# Decoder_35.net
KiCad netlist of a schematic drawn in EAGLE
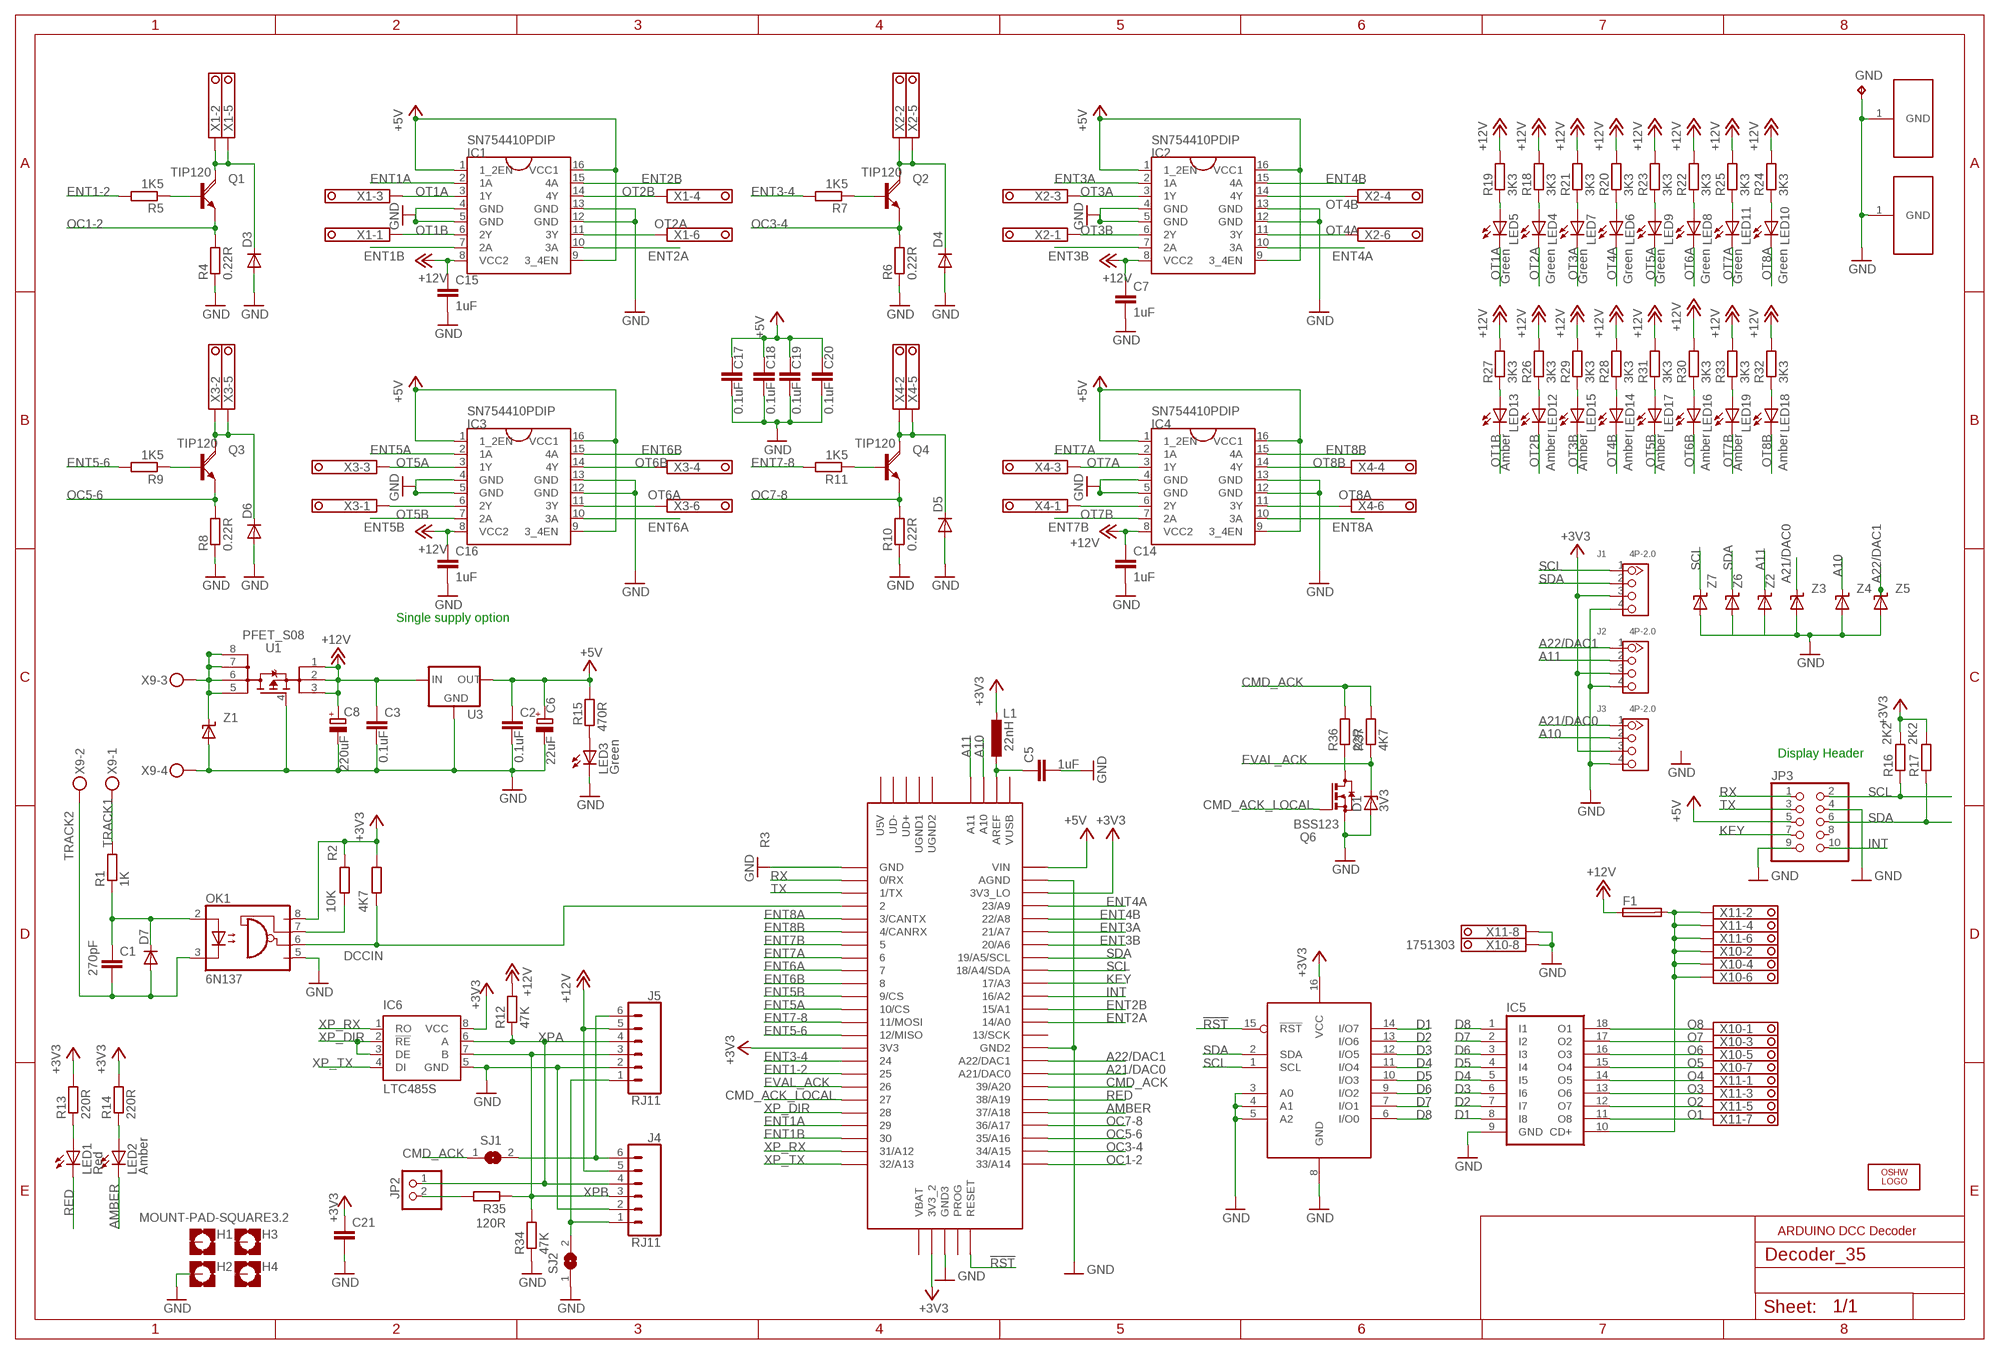
[diagram p0: schematic, sheet 1]

(export (version "E")
  (design (tool "Eeschema 10.0.6"))
  (components
    (comp (ref "C1")
      (value "270pF")
      (footprint "eagle-import:C0805")
      (libsource (lib "eagle-import") (part "rcl_334_C-EUC0805"))
    )
    (comp (ref "C2")
      (value "0.1uF")
      (footprint "eagle-import:C0805")
      (libsource (lib "eagle-import") (part "rcl_334_C-EUC0805"))
    )
    (comp (ref "C3")
      (value "0.1uF")
      (footprint "eagle-import:C0805")
      (libsource (lib "eagle-import") (part "rcl_334_C-EUC0805"))
    )
    (comp (ref "C5")
      (value "1uF")
      (footprint "eagle-import:C0805")
      (libsource (lib "eagle-import") (part "rcl_334_C-EUC0805"))
    )
    (comp (ref "C6")
      (value "22uF")
      (footprint "eagle-import:E2,5-5")
      (libsource (lib "eagle-import") (part "CPOL-EUE2.5-5"))
    )
    (comp (ref "C7")
      (value "1uF")
      (footprint "eagle-import:C0805")
      (libsource (lib "eagle-import") (part "rcl_334_C-EUC0805"))
    )
    (comp (ref "C8")
      (value "220uF")
      (footprint "eagle-import:E5-8,5")
      (libsource (lib "eagle-import") (part "CPOL-EUE5-8.5"))
    )
    (comp (ref "C14")
      (value "1uF")
      (footprint "eagle-import:C0805")
      (libsource (lib "eagle-import") (part "rcl_334_C-EUC0805"))
    )
    (comp (ref "C15")
      (value "1uF")
      (footprint "eagle-import:C0805")
      (libsource (lib "eagle-import") (part "rcl_334_C-EUC0805"))
    )
    (comp (ref "C16")
      (value "1uF")
      (footprint "eagle-import:C0805")
      (libsource (lib "eagle-import") (part "rcl_334_C-EUC0805"))
    )
    (comp (ref "C17")
      (value "0.1uF")
      (footprint "eagle-import:C0805")
      (libsource (lib "eagle-import") (part "rcl_334_C-EUC0805"))
    )
    (comp (ref "C18")
      (value "0.1uF")
      (footprint "eagle-import:C0805")
      (libsource (lib "eagle-import") (part "rcl_334_C-EUC0805"))
    )
    (comp (ref "C19")
      (value "0.1uF")
      (footprint "eagle-import:C0805")
      (libsource (lib "eagle-import") (part "rcl_334_C-EUC0805"))
    )
    (comp (ref "C20")
      (value "0.1uF")
      (footprint "eagle-import:C0805")
      (libsource (lib "eagle-import") (part "rcl_334_C-EUC0805"))
    )
    (comp (ref "C21")
      (value "C-EUC0805")
      (footprint "eagle-import:C0805")
      (libsource (lib "eagle-import") (part "C-EUC0805"))
    )
    (comp (ref "D1")
      (value "3V3")
      (footprint "eagle-import:SOT23")
      (libsource (lib "eagle-import") (part "ZENER-DIODESOT23"))
    )
    (comp (ref "D3")
      (value "CGRM4002-G")
      (footprint "eagle-import:SOD-123_MINI-SMA")
      (libsource (lib "eagle-import") (part "CGRM400-G2"))
    )
    (comp (ref "D4")
      (value "CGRM4002-G")
      (footprint "eagle-import:SOD-123_MINI-SMA")
      (libsource (lib "eagle-import") (part "CGRM400-G2"))
    )
    (comp (ref "D5")
      (value "CGRM4002-G")
      (footprint "eagle-import:SOD-123_MINI-SMA")
      (libsource (lib "eagle-import") (part "CGRM400-G2"))
    )
    (comp (ref "D6")
      (value "CGRM4002-G")
      (footprint "eagle-import:SOD-123_MINI-SMA")
      (libsource (lib "eagle-import") (part "CGRM400-G2"))
    )
    (comp (ref "D7")
      (value "CGRM4002-G")
      (footprint "eagle-import:SOD-123_MINI-SMA")
      (libsource (lib "eagle-import") (part "CGRM400-G2"))
    )
    (comp (ref "F1")
      (value "SMD_FUSE")
      (footprint "eagle-import:1812")
      (fields (field (name "MANUFACTURER") "Littelfuse"))
      (libsource (lib "eagle-import") (part "SMD_FUSE"))
    )
    (comp (ref "GND")
      (value "TPB2,54")
      (footprint "eagle-import:B2,54")
      (libsource (lib "eagle-import") (part "TPB2,54"))
    )
    (comp (ref "H1")
      (value "MOUNT-PAD-SQUARE3.2")
      (footprint "eagle-import:3,2-PAD-SQUARE")
      (libsource (lib "eagle-import") (part "MOUNT-PAD-SQUARE3.2"))
    )
    (comp (ref "H2")
      (value "MOUNT-PAD-SQUARE3.2")
      (footprint "eagle-import:3,2-PAD-SQUARE")
      (libsource (lib "eagle-import") (part "MOUNT-PAD-SQUARE3.2"))
    )
    (comp (ref "H3")
      (value "MOUNT-PAD-SQUARE3.2")
      (footprint "eagle-import:3,2-PAD-SQUARE")
      (libsource (lib "eagle-import") (part "MOUNT-PAD-SQUARE3.2"))
    )
    (comp (ref "H4")
      (value "MOUNT-PAD-SQUARE3.2")
      (footprint "eagle-import:3,2-PAD-SQUARE")
      (libsource (lib "eagle-import") (part "MOUNT-PAD-SQUARE3.2"))
    )
    (comp (ref "IC1")
      (value "SN754410PDIP")
      (footprint "eagle-import:DIL16")
      (libsource (lib "eagle-import") (part "SN754410PDIP"))
    )
    (comp (ref "IC2")
      (value "SN754410PDIP")
      (footprint "eagle-import:DIL16")
      (libsource (lib "eagle-import") (part "SN754410PDIP"))
    )
    (comp (ref "IC3")
      (value "SN754410PDIP")
      (footprint "eagle-import:DIL16")
      (libsource (lib "eagle-import") (part "SN754410PDIP"))
    )
    (comp (ref "IC4")
      (value "SN754410PDIP")
      (footprint "eagle-import:DIL16")
      (libsource (lib "eagle-import") (part "SN754410PDIP"))
    )
    (comp (ref "IC5")
      (value "ULN2803A")
      (footprint "eagle-import:DIL18")
      (libsource (lib "eagle-import") (part "ULN2803A"))
    )
    (comp (ref "IC6")
      (value "LTC485S")
      (footprint "eagle-import:SOIC8")
      (libsource (lib "eagle-import") (part "LTC485S"))
    )
    (comp (ref "J1")
      (value "4P-2.0")
      (footprint "eagle-import:HW4-2.0")
      (libsource (lib "eagle-import") (part "GROVE-CONNECTOR-DIP(4P-2.0)"))
    )
    (comp (ref "J2")
      (value "4P-2.0")
      (footprint "eagle-import:HW4-2.0")
      (libsource (lib "eagle-import") (part "GROVE-CONNECTOR-DIP(4P-2.0)"))
    )
    (comp (ref "J3")
      (value "4P-2.0")
      (footprint "eagle-import:HW4-2.0")
      (libsource (lib "eagle-import") (part "GROVE-CONNECTOR-DIP(4P-2.0)"))
    )
    (comp (ref "J4")
      (value "RJ11")
      (footprint "eagle-import:RJ11-6")
      (libsource (lib "eagle-import") (part "RJ11-6"))
    )
    (comp (ref "J5")
      (value "RJ11")
      (footprint "eagle-import:RJ11-6")
      (libsource (lib "eagle-import") (part "RJ11-6"))
    )
    (comp (ref "JP2")
      (value "PINHD-1X2")
      (footprint "eagle-import:1X02")
      (libsource (lib "eagle-import") (part "PINHD-1X2"))
    )
    (comp (ref "JP3")
      (value "PINHD-2X5")
      (footprint "eagle-import:2X05")
      (libsource (lib "eagle-import") (part "PINHD-2X5"))
    )
    (comp (ref "L1")
      (value "22nH")
      (footprint "eagle-import:L2012C")
      (libsource (lib "eagle-import") (part "L-EUL2012C"))
    )
    (comp (ref "LED1")
      (value "Red")
      (footprint "eagle-import:LED3MM")
      (libsource (lib "eagle-import") (part "LED3MM"))
    )
    (comp (ref "LED2")
      (value "Amber")
      (footprint "eagle-import:LED3MM")
      (libsource (lib "eagle-import") (part "LED3MM"))
    )
    (comp (ref "LED3")
      (value "Green")
      (footprint "eagle-import:LED3MM")
      (libsource (lib "eagle-import") (part "LED3MM"))
    )
    (comp (ref "LED4")
      (value "Green")
      (footprint "eagle-import:LED3MM")
      (libsource (lib "eagle-import") (part "LED3MM"))
    )
    (comp (ref "LED5")
      (value "Green")
      (footprint "eagle-import:LED3MM")
      (libsource (lib "eagle-import") (part "LED3MM"))
    )
    (comp (ref "LED6")
      (value "Green")
      (footprint "eagle-import:LED3MM")
      (libsource (lib "eagle-import") (part "LED3MM"))
    )
    (comp (ref "LED7")
      (value "Green")
      (footprint "eagle-import:LED3MM")
      (libsource (lib "eagle-import") (part "LED3MM"))
    )
    (comp (ref "LED8")
      (value "Green")
      (footprint "eagle-import:LED3MM")
      (libsource (lib "eagle-import") (part "LED3MM"))
    )
    (comp (ref "LED9")
      (value "Green")
      (footprint "eagle-import:LED3MM")
      (libsource (lib "eagle-import") (part "LED3MM"))
    )
    (comp (ref "LED10")
      (value "Green")
      (footprint "eagle-import:LED3MM")
      (libsource (lib "eagle-import") (part "LED3MM"))
    )
    (comp (ref "LED11")
      (value "Green")
      (footprint "eagle-import:LED3MM")
      (libsource (lib "eagle-import") (part "LED3MM"))
    )
    (comp (ref "LED12")
      (value "Amber")
      (footprint "eagle-import:LED3MM")
      (libsource (lib "eagle-import") (part "LED3MM"))
    )
    (comp (ref "LED13")
      (value "Amber")
      (footprint "eagle-import:LED3MM")
      (libsource (lib "eagle-import") (part "LED3MM"))
    )
    (comp (ref "LED14")
      (value "Amber")
      (footprint "eagle-import:LED3MM")
      (libsource (lib "eagle-import") (part "LED3MM"))
    )
    (comp (ref "LED15")
      (value "Amber")
      (footprint "eagle-import:LED3MM")
      (libsource (lib "eagle-import") (part "LED3MM"))
    )
    (comp (ref "LED16")
      (value "Amber")
      (footprint "eagle-import:LED3MM")
      (libsource (lib "eagle-import") (part "LED3MM"))
    )
    (comp (ref "LED17")
      (value "Amber")
      (footprint "eagle-import:LED3MM")
      (libsource (lib "eagle-import") (part "LED3MM"))
    )
    (comp (ref "LED18")
      (value "Amber")
      (footprint "eagle-import:LED3MM")
      (libsource (lib "eagle-import") (part "LED3MM"))
    )
    (comp (ref "LED19")
      (value "Amber")
      (footprint "eagle-import:LED3MM")
      (libsource (lib "eagle-import") (part "LED3MM"))
    )
    (comp (ref "LOGO1")
      (value "OSHW_LOGO_6MILX0200-NT")
      (footprint "eagle-import:OSHW_6X200_NOTEXT")
      (libsource (lib "eagle-import") (part "OSHW_LOGO_6MILX0200-NT"))
    )
    (comp (ref "MT1")
      (value "DINC45_MOUNT")
      (footprint "eagle-import:DIN_C45")
      (libsource (lib "eagle-import") (part "DINC45_MOUNT"))
    )
    (comp (ref "MT2")
      (value "DINC45_MOUNT")
      (footprint "eagle-import:DIN_C45")
      (libsource (lib "eagle-import") (part "DINC45_MOUNT"))
    )
    (comp (ref "OK1")
      (value "6N137")
      (footprint "eagle-import:DIL08")
      (libsource (lib "eagle-import") (part "6N137"))
    )
    (comp (ref "Q1")
      (value "TIP120")
      (footprint "eagle-import:TO220AH")
      (libsource (lib "eagle-import") (part "TIP120"))
    )
    (comp (ref "Q2")
      (value "TIP120")
      (footprint "eagle-import:TO220AH")
      (libsource (lib "eagle-import") (part "TIP120"))
    )
    (comp (ref "Q3")
      (value "TIP120")
      (footprint "eagle-import:TO220AH")
      (libsource (lib "eagle-import") (part "TIP120"))
    )
    (comp (ref "Q4")
      (value "TIP120")
      (footprint "eagle-import:TO220AH")
      (libsource (lib "eagle-import") (part "TIP120"))
    )
    (comp (ref "Q6")
      (value "BSS123")
      (footprint "eagle-import:SOT23")
      (libsource (lib "eagle-import") (part "BSS123"))
    )
    (comp (ref "R1")
      (value "1K")
      (footprint "eagle-import:R0805")
      (libsource (lib "eagle-import") (part "rcl_334_R-EU_R0805"))
    )
    (comp (ref "R2")
      (value "10K")
      (footprint "eagle-import:R0805")
      (libsource (lib "eagle-import") (part "rcl_334_R-EU_R0805"))
    )
    (comp (ref "R3")
      (value "4K7")
      (footprint "eagle-import:R0805")
      (libsource (lib "eagle-import") (part "rcl_334_R-EU_R0805"))
    )
    (comp (ref "R4")
      (value "0.22R")
      (footprint "eagle-import:R2512")
      (libsource (lib "eagle-import") (part "rcl_334_R-EU_R2512"))
    )
    (comp (ref "R5")
      (value "1K5")
      (footprint "eagle-import:R0805")
      (libsource (lib "eagle-import") (part "rcl_334_R-EU_R0805"))
    )
    (comp (ref "R6")
      (value "0.22R")
      (footprint "eagle-import:R2512")
      (libsource (lib "eagle-import") (part "rcl_334_R-EU_R2512"))
    )
    (comp (ref "R7")
      (value "1K5")
      (footprint "eagle-import:R0805")
      (libsource (lib "eagle-import") (part "rcl_334_R-EU_R0805"))
    )
    (comp (ref "R8")
      (value "0.22R")
      (footprint "eagle-import:R2512")
      (libsource (lib "eagle-import") (part "rcl_334_R-EU_R2512"))
    )
    (comp (ref "R9")
      (value "1K5")
      (footprint "eagle-import:R0805")
      (libsource (lib "eagle-import") (part "rcl_334_R-EU_R0805"))
    )
    (comp (ref "R10")
      (value "0.22R")
      (footprint "eagle-import:R2512")
      (libsource (lib "eagle-import") (part "rcl_334_R-EU_R2512"))
    )
    (comp (ref "R11")
      (value "1K5")
      (footprint "eagle-import:R0805")
      (libsource (lib "eagle-import") (part "rcl_334_R-EU_R0805"))
    )
    (comp (ref "R12")
      (value "47K")
      (footprint "eagle-import:R0805")
      (libsource (lib "eagle-import") (part "R-EU_R0805"))
    )
    (comp (ref "R13")
      (value "220R")
      (footprint "eagle-import:R0805")
      (libsource (lib "eagle-import") (part "rcl_334_R-EU_R0805"))
    )
    (comp (ref "R14")
      (value "220R")
      (footprint "eagle-import:R0805")
      (libsource (lib "eagle-import") (part "rcl_334_R-EU_R0805"))
    )
    (comp (ref "R15")
      (value "470R")
      (footprint "eagle-import:R0805")
      (libsource (lib "eagle-import") (part "rcl_334_R-EU_R0805"))
    )
    (comp (ref "R16")
      (value "2K2")
      (footprint "eagle-import:R0805")
      (libsource (lib "eagle-import") (part "rcl_334_R-EU_R0805"))
    )
    (comp (ref "R17")
      (value "2K2")
      (footprint "eagle-import:R0805")
      (libsource (lib "eagle-import") (part "rcl_334_R-EU_R0805"))
    )
    (comp (ref "R18")
      (value "3K3")
      (footprint "eagle-import:R0805")
      (libsource (lib "eagle-import") (part "rcl_334_R-EU_R0805"))
    )
    (comp (ref "R19")
      (value "3K3")
      (footprint "eagle-import:R0805")
      (libsource (lib "eagle-import") (part "rcl_334_R-EU_R0805"))
    )
    (comp (ref "R20")
      (value "3K3")
      (footprint "eagle-import:R0805")
      (libsource (lib "eagle-import") (part "rcl_334_R-EU_R0805"))
    )
    (comp (ref "R21")
      (value "3K3")
      (footprint "eagle-import:R0805")
      (libsource (lib "eagle-import") (part "rcl_334_R-EU_R0805"))
    )
    (comp (ref "R22")
      (value "3K3")
      (footprint "eagle-import:R0805")
      (libsource (lib "eagle-import") (part "rcl_334_R-EU_R0805"))
    )
    (comp (ref "R23")
      (value "3K3")
      (footprint "eagle-import:R0805")
      (libsource (lib "eagle-import") (part "rcl_334_R-EU_R0805"))
    )
    (comp (ref "R24")
      (value "3K3")
      (footprint "eagle-import:R0805")
      (libsource (lib "eagle-import") (part "rcl_334_R-EU_R0805"))
    )
    (comp (ref "R25")
      (value "3K3")
      (footprint "eagle-import:R0805")
      (libsource (lib "eagle-import") (part "rcl_334_R-EU_R0805"))
    )
    (comp (ref "R26")
      (value "3K3")
      (footprint "eagle-import:R0805")
      (libsource (lib "eagle-import") (part "rcl_334_R-EU_R0805"))
    )
    (comp (ref "R27")
      (value "3K3")
      (footprint "eagle-import:R0805")
      (libsource (lib "eagle-import") (part "rcl_334_R-EU_R0805"))
    )
    (comp (ref "R28")
      (value "3K3")
      (footprint "eagle-import:R0805")
      (libsource (lib "eagle-import") (part "rcl_334_R-EU_R0805"))
    )
    (comp (ref "R29")
      (value "3K3")
      (footprint "eagle-import:R0805")
      (libsource (lib "eagle-import") (part "rcl_334_R-EU_R0805"))
    )
    (comp (ref "R30")
      (value "3K3")
      (footprint "eagle-import:R0805")
      (libsource (lib "eagle-import") (part "rcl_334_R-EU_R0805"))
    )
    (comp (ref "R31")
      (value "3K3")
      (footprint "eagle-import:R0805")
      (libsource (lib "eagle-import") (part "rcl_334_R-EU_R0805"))
    )
    (comp (ref "R32")
      (value "3K3")
      (footprint "eagle-import:R0805")
      (libsource (lib "eagle-import") (part "rcl_334_R-EU_R0805"))
    )
    (comp (ref "R33")
      (value "3K3")
      (footprint "eagle-import:R0805")
      (libsource (lib "eagle-import") (part "rcl_334_R-EU_R0805"))
    )
    (comp (ref "R34")
      (value "47K")
      (footprint "eagle-import:R0805")
      (libsource (lib "eagle-import") (part "R-EU_R0805"))
    )
    (comp (ref "R35")
      (value "120R")
      (footprint "eagle-import:R0805")
      (libsource (lib "eagle-import") (part "R-EU_R0805"))
    )
    (comp (ref "R36")
      (value "22R")
      (footprint "eagle-import:R0805")
      (libsource (lib "eagle-import") (part "R-EU_R0805"))
    )
    (comp (ref "R37")
      (value "4K7")
      (footprint "eagle-import:R0805")
      (libsource (lib "eagle-import") (part "R-EU_R0805"))
    )
    (comp (ref "SJ1") (value "SJ") (footprint "eagle-import:SJ") (libsource (lib "eagle-import") (part "SJ")))
    (comp (ref "SJ2") (value "SJ") (footprint "eagle-import:SJ") (libsource (lib "eagle-import") (part "SJ")))
    (comp (ref "U$1")
      (value "TEENSY_3.5/3.6")
      (footprint "eagle-import:TEENSY_3.5_3.6")
      (libsource (lib "eagle-import") (part "TEENSY_3.5/3.6"))
    )
    (comp (ref "U1")
      (value "PFET_S08")
      (footprint "eagle-import:SO08")
      (fields (field (name "MANUFACTURER") "Infineon") (field (name "PARTNUMBER") "IRF9388TRFPBF"))
      (libsource (lib "eagle-import") (part "PFET_S08"))
    )
    (comp (ref "U2")
      (value "PCA9557")
      (footprint "eagle-import:S016")
      (libsource (lib "eagle-import") (part "PCA9557"))
    )
    (comp (ref "U3")
      (value "V_REG_78XX-TO-220")
      (footprint "eagle-import:TO-220-ALT")
      (libsource (lib "eagle-import") (part "V_REG_78XX-TO-220"))
    )
    (comp (ref "X1")
      (value "1751280")
      (footprint "eagle-import:1751280")
      (libsource (lib "eagle-import") (part "1751280"))
    )
    (comp (ref "X2")
      (value "1751280")
      (footprint "eagle-import:1751280")
      (libsource (lib "eagle-import") (part "1751280"))
    )
    (comp (ref "X3")
      (value "1751280")
      (footprint "eagle-import:1751280")
      (libsource (lib "eagle-import") (part "1751280"))
    )
    (comp (ref "X4")
      (value "1751280")
      (footprint "eagle-import:1751280")
      (libsource (lib "eagle-import") (part "1751280"))
    )
    (comp (ref "X9")
      (value "MKDSN1,5/4-5,08")
      (footprint "eagle-import:MKDSN1,5_4-5,08")
      (libsource (lib "eagle-import") (part "MKDSN1,5/4-5,08"))
    )
    (comp (ref "X10")
      (value "1751303")
      (footprint "eagle-import:1751303")
      (libsource (lib "eagle-import") (part "1751303"))
    )
    (comp (ref "X11")
      (value "1751303")
      (footprint "eagle-import:1751303")
      (libsource (lib "eagle-import") (part "1751303"))
    )
    (comp (ref "Z1")
      (value "TRANSZORB")
      (footprint "eagle-import:SMB")
      (fields (field (name "VOLTAGE") "15V"))
      (libsource (lib "eagle-import") (part "TRANSZORB"))
    )
    (comp (ref "Z2")
      (value "TRANSZORB-SMA")
      (footprint "eagle-import:SMA")
      (libsource (lib "eagle-import") (part "TRANSZORB-SMA"))
    )
    (comp (ref "Z3")
      (value "TRANSZORB-SMA")
      (footprint "eagle-import:SMA")
      (libsource (lib "eagle-import") (part "TRANSZORB-SMA"))
    )
    (comp (ref "Z4")
      (value "TRANSZORB-SMA")
      (footprint "eagle-import:SMA")
      (libsource (lib "eagle-import") (part "TRANSZORB-SMA"))
    )
    (comp (ref "Z5")
      (value "TRANSZORB-SMA")
      (footprint "eagle-import:SMA")
      (libsource (lib "eagle-import") (part "TRANSZORB-SMA"))
    )
    (comp (ref "Z6")
      (value "TRANSZORB-SMA")
      (footprint "eagle-import:SMA")
      (libsource (lib "eagle-import") (part "TRANSZORB-SMA"))
    )
    (comp (ref "Z7")
      (value "TRANSZORB-SMA")
      (footprint "eagle-import:SMA")
      (libsource (lib "eagle-import") (part "TRANSZORB-SMA"))
    )
  )
  (nets
    (net (code "1") (name "+3V3") (class "Default")
      (node (ref "C21") (pin "1") (pinfunction "1_1") (pintype "passive"))
      (node (ref "IC6") (pin "8") (pinfunction "VCC_8") (pintype "input"))
      (node (ref "J1") (pin "3") (pinfunction "3_3") (pintype "bidirectional"))
      (node (ref "J2") (pin "3") (pinfunction "3_3") (pintype "bidirectional"))
      (node (ref "J3") (pin "3") (pinfunction "3_3") (pintype "bidirectional"))
      (node (ref "L1") (pin "1") (pinfunction "1_1") (pintype "passive"))
      (node (ref "OK1") (pin "8") (pinfunction "VCC_8") (pintype "passive"))
      (node (ref "R13") (pin "2") (pinfunction "2_2") (pintype "passive"))
      (node (ref "R14") (pin "2") (pinfunction "2_2") (pintype "passive"))
      (node (ref "R16") (pin "2") (pinfunction "2_2") (pintype "passive"))
      (node (ref "R17") (pin "2") (pinfunction "2_2") (pintype "passive"))
      (node (ref "R2") (pin "2") (pinfunction "2_2") (pintype "passive"))
      (node (ref "R3") (pin "2") (pinfunction "2_2") (pintype "passive"))
      (node (ref "U$1") (pin "3V3") (pinfunction "3V3_3V3") (pintype "bidirectional"))
      (node (ref "U$1") (pin "3V3_2") (pinfunction "3V3_2_3V3_2") (pintype "bidirectional"))
      (node (ref "U$1") (pin "3V3_LO") (pinfunction "3V3_LO_3V3_LO") (pintype "bidirectional"))
      (node (ref "U2") (pin "16") (pinfunction "VCC_16") (pintype "power_in"))
    )
    (net (code "2") (name "+5V") (class "Default")
      (node (ref "C17") (pin "1") (pinfunction "1_1") (pintype "passive"))
      (node (ref "C18") (pin "1") (pinfunction "1_1") (pintype "passive"))
      (node (ref "C19") (pin "1") (pinfunction "1_1") (pintype "passive"))
      (node (ref "C2") (pin "1") (pinfunction "1_1") (pintype "passive"))
      (node (ref "C20") (pin "1") (pinfunction "1_1") (pintype "passive"))
      (node (ref "C6") (pin "+") (pinfunction "+_+") (pintype "passive"))
      (node (ref "IC1") (pin "1") (pinfunction "1_2EN_1") (pintype "bidirectional"))
      (node (ref "IC1") (pin "16") (pinfunction "VCC1_16") (pintype "bidirectional"))
      (node (ref "IC1") (pin "9") (pinfunction "3_4EN_9") (pintype "bidirectional"))
      (node (ref "IC2") (pin "1") (pinfunction "1_2EN_1") (pintype "bidirectional"))
      (node (ref "IC2") (pin "16") (pinfunction "VCC1_16") (pintype "bidirectional"))
      (node (ref "IC2") (pin "9") (pinfunction "3_4EN_9") (pintype "bidirectional"))
      (node (ref "IC3") (pin "1") (pinfunction "1_2EN_1") (pintype "bidirectional"))
      (node (ref "IC3") (pin "16") (pinfunction "VCC1_16") (pintype "bidirectional"))
      (node (ref "IC3") (pin "9") (pinfunction "3_4EN_9") (pintype "bidirectional"))
      (node (ref "IC4") (pin "1") (pinfunction "1_2EN_1") (pintype "bidirectional"))
      (node (ref "IC4") (pin "16") (pinfunction "VCC1_16") (pintype "bidirectional"))
      (node (ref "IC4") (pin "9") (pinfunction "3_4EN_9") (pintype "bidirectional"))
      (node (ref "JP3") (pin "5") (pinfunction "5_5") (pintype "passive"))
      (node (ref "R15") (pin "2") (pinfunction "2_2") (pintype "passive"))
      (node (ref "U$1") (pin "VIN") (pinfunction "VIN_VIN") (pintype "bidirectional"))
      (node (ref "U3") (pin "OUT") (pinfunction "OUT_OUT") (pintype "passive"))
    )
    (net (code "3") (name "+12V") (class "Default")
      (node (ref "C14") (pin "1") (pinfunction "1_1") (pintype "passive"))
      (node (ref "C15") (pin "1") (pinfunction "1_1") (pintype "passive"))
      (node (ref "C16") (pin "1") (pinfunction "1_1") (pintype "passive"))
      (node (ref "C3") (pin "1") (pinfunction "1_1") (pintype "passive"))
      (node (ref "C7") (pin "1") (pinfunction "1_1") (pintype "passive"))
      (node (ref "C8") (pin "+") (pinfunction "+_+") (pintype "passive"))
      (node (ref "F1") (pin "1") (pinfunction "1_1") (pintype "passive"))
      (node (ref "IC1") (pin "8") (pinfunction "VCC2_8") (pintype "bidirectional"))
      (node (ref "IC2") (pin "8") (pinfunction "VCC2_8") (pintype "bidirectional"))
      (node (ref "IC3") (pin "8") (pinfunction "VCC2_8") (pintype "bidirectional"))
      (node (ref "IC4") (pin "8") (pinfunction "VCC2_8") (pintype "bidirectional"))
      (node (ref "J4") (pin "5") (pinfunction "5_5") (pintype "passive"))
      (node (ref "J5") (pin "5") (pinfunction "5_5") (pintype "passive"))
      (node (ref "R12") (pin "2") (pinfunction "2_2") (pintype "passive"))
      (node (ref "R18") (pin "2") (pinfunction "2_2") (pintype "passive"))
      (node (ref "R19") (pin "2") (pinfunction "2_2") (pintype "passive"))
      (node (ref "R20") (pin "2") (pinfunction "2_2") (pintype "passive"))
      (node (ref "R21") (pin "2") (pinfunction "2_2") (pintype "passive"))
      (node (ref "R22") (pin "2") (pinfunction "2_2") (pintype "passive"))
      (node (ref "R23") (pin "2") (pinfunction "2_2") (pintype "passive"))
      (node (ref "R24") (pin "2") (pinfunction "2_2") (pintype "passive"))
      (node (ref "R25") (pin "2") (pinfunction "2_2") (pintype "passive"))
      (node (ref "R26") (pin "2") (pinfunction "2_2") (pintype "passive"))
      (node (ref "R27") (pin "2") (pinfunction "2_2") (pintype "passive"))
      (node (ref "R28") (pin "2") (pinfunction "2_2") (pintype "passive"))
      (node (ref "R29") (pin "2") (pinfunction "2_2") (pintype "passive"))
      (node (ref "R30") (pin "2") (pinfunction "2_2") (pintype "passive"))
      (node (ref "R31") (pin "2") (pinfunction "2_2") (pintype "passive"))
      (node (ref "R32") (pin "2") (pinfunction "2_2") (pintype "passive"))
      (node (ref "R33") (pin "2") (pinfunction "2_2") (pintype "passive"))
      (node (ref "U1") (pin "1") (pinfunction "S1_1") (pintype "passive"))
      (node (ref "U1") (pin "2") (pinfunction "S2_2") (pintype "passive"))
      (node (ref "U1") (pin "3") (pinfunction "S3_3") (pintype "passive"))
      (node (ref "U3") (pin "IN") (pinfunction "IN_IN") (pintype "input"))
    )
    (net (code "4") (name "/A10") (class "Default")
      (node (ref "J3") (pin "2") (pinfunction "2_2") (pintype "bidirectional"))
      (node (ref "U$1") (pin "A10") (pinfunction "A10_A10") (pintype "bidirectional"))
      (node (ref "Z4") (pin "C") (pinfunction "C_C") (pintype "passive"))
    )
    (net (code "5") (name "/A11") (class "Default")
      (node (ref "J2") (pin "2") (pinfunction "2_2") (pintype "bidirectional"))
      (node (ref "U$1") (pin "A11") (pinfunction "A11_A11") (pintype "bidirectional"))
      (node (ref "Z2") (pin "C") (pinfunction "C_C") (pintype "passive"))
    )
    (net (code "6") (name "/A21{slash}DAC0") (class "Default")
      (node (ref "J3") (pin "1") (pinfunction "1_1") (pintype "bidirectional"))
      (node (ref "U$1") (pin "21/DAC0") (pinfunction "A21/DAC0_21/DAC0") (pintype "bidirectional"))
      (node (ref "Z3") (pin "C") (pinfunction "C_C") (pintype "passive"))
    )
    (net (code "7") (name "/A22{slash}DAC1") (class "Default")
      (node (ref "J2") (pin "1") (pinfunction "1_1") (pintype "bidirectional"))
      (node (ref "U$1") (pin "A22/DAC1") (pinfunction "A22/DAC1_A22/DAC1") (pintype "bidirectional"))
      (node (ref "Z5") (pin "C") (pinfunction "C_C") (pintype "passive"))
    )
    (net (code "8") (name "/AMBER") (class "Default")
      (node (ref "LED2") (pin "K") (pinfunction "C_K") (pintype "passive"))
      (node (ref "U$1") (pin "37/A18") (pinfunction "37/A18_37/A18") (pintype "bidirectional"))
    )
    (net (code "9") (name "/CMD_ACK") (class "Default")
      (node (ref "R36") (pin "2") (pinfunction "2_2") (pintype "passive"))
      (node (ref "R37") (pin "2") (pinfunction "2_2") (pintype "passive"))
      (node (ref "SJ1") (pin "1") (pinfunction "1_1") (pintype "passive"))
      (node (ref "U$1") (pin "39/A20") (pinfunction "39/A20_39/A20") (pintype "bidirectional"))
    )
    (net (code "10") (name "/CMD_ACK_LOCAL") (class "Default")
      (node (ref "Q6") (pin "1") (pinfunction "G_1") (pintype "passive"))
      (node (ref "U$1") (pin "27") (pinfunction "27_27") (pintype "bidirectional"))
    )
    (net (code "11") (name "/D1") (class "Default")
      (node (ref "IC5") (pin "8") (pinfunction "I8_8") (pintype "input"))
      (node (ref "U2") (pin "14") (pinfunction "I/O7_14") (pintype "bidirectional"))
    )
    (net (code "12") (name "/D2") (class "Default")
      (node (ref "IC5") (pin "7") (pinfunction "I7_7") (pintype "input"))
      (node (ref "U2") (pin "13") (pinfunction "I/O6_13") (pintype "bidirectional"))
    )
    (net (code "13") (name "/D3") (class "Default")
      (node (ref "IC5") (pin "6") (pinfunction "I6_6") (pintype "input"))
      (node (ref "U2") (pin "12") (pinfunction "I/O5_12") (pintype "bidirectional"))
    )
    (net (code "14") (name "/D4") (class "Default")
      (node (ref "IC5") (pin "5") (pinfunction "I5_5") (pintype "input"))
      (node (ref "U2") (pin "11") (pinfunction "I/O4_11") (pintype "bidirectional"))
    )
    (net (code "15") (name "/D5") (class "Default")
      (node (ref "IC5") (pin "4") (pinfunction "I4_4") (pintype "input"))
      (node (ref "U2") (pin "10") (pinfunction "I/O3_10") (pintype "bidirectional"))
    )
    (net (code "16") (name "/D6") (class "Default")
      (node (ref "IC5") (pin "3") (pinfunction "I3_3") (pintype "input"))
      (node (ref "U2") (pin "9") (pinfunction "I/O2_9") (pintype "bidirectional"))
    )
    (net (code "17") (name "/D7") (class "Default")
      (node (ref "IC5") (pin "2") (pinfunction "I2_2") (pintype "input"))
      (node (ref "U2") (pin "7") (pinfunction "I/O1_7") (pintype "bidirectional"))
    )
    (net (code "18") (name "/D8") (class "Default")
      (node (ref "IC5") (pin "1") (pinfunction "I1_1") (pintype "input"))
      (node (ref "U2") (pin "6") (pinfunction "I/O0_6") (pintype "bidirectional"))
    )
    (net (code "19") (name "/DCCIN") (class "Default")
      (node (ref "OK1") (pin "6") (pinfunction "VO_6") (pintype "passive"))
      (node (ref "R3") (pin "1") (pinfunction "1_1") (pintype "passive"))
      (node (ref "U$1") (pin "2") (pinfunction "2_2") (pintype "bidirectional"))
    )
    (net (code "20") (name "/ENT1-2") (class "Default")
      (node (ref "R5") (pin "2") (pinfunction "2_2") (pintype "passive"))
      (node (ref "U$1") (pin "25") (pinfunction "25_25") (pintype "bidirectional"))
    )
    (net (code "21") (name "/ENT1A") (class "Default")
      (node (ref "IC1") (pin "2") (pinfunction "1A_2") (pintype "bidirectional"))
      (node (ref "U$1") (pin "29") (pinfunction "29_29") (pintype "bidirectional"))
    )
    (net (code "22") (name "/ENT1B") (class "Default")
      (node (ref "IC1") (pin "7") (pinfunction "2A_7") (pintype "bidirectional"))
      (node (ref "U$1") (pin "30") (pinfunction "30_30") (pintype "bidirectional"))
    )
    (net (code "23") (name "/ENT2A") (class "Default")
      (node (ref "IC1") (pin "10") (pinfunction "3A_10") (pintype "bidirectional"))
      (node (ref "U$1") (pin "14/A0") (pinfunction "14/A0_14/A0") (pintype "bidirectional"))
    )
    (net (code "24") (name "/ENT2B") (class "Default")
      (node (ref "IC1") (pin "15") (pinfunction "4A_15") (pintype "bidirectional"))
      (node (ref "U$1") (pin "15/A1") (pinfunction "15/A1_15/A1") (pintype "bidirectional"))
    )
    (net (code "25") (name "/ENT3-4") (class "Default")
      (node (ref "R7") (pin "2") (pinfunction "2_2") (pintype "passive"))
      (node (ref "U$1") (pin "24") (pinfunction "24_24") (pintype "bidirectional"))
    )
    (net (code "26") (name "/ENT3A") (class "Default")
      (node (ref "IC2") (pin "2") (pinfunction "1A_2") (pintype "bidirectional"))
      (node (ref "U$1") (pin "21/A7") (pinfunction "21/A7_21/A7") (pintype "bidirectional"))
    )
    (net (code "27") (name "/ENT3B") (class "Default")
      (node (ref "IC2") (pin "7") (pinfunction "2A_7") (pintype "bidirectional"))
      (node (ref "U$1") (pin "20/A6") (pinfunction "20/A6_20/A6") (pintype "bidirectional"))
    )
    (net (code "28") (name "/ENT4A") (class "Default")
      (node (ref "IC2") (pin "10") (pinfunction "3A_10") (pintype "bidirectional"))
      (node (ref "U$1") (pin "23/A9") (pinfunction "23/A9_23/A9") (pintype "bidirectional"))
    )
    (net (code "29") (name "/ENT4B") (class "Default")
      (node (ref "IC2") (pin "15") (pinfunction "4A_15") (pintype "bidirectional"))
      (node (ref "U$1") (pin "22/A8") (pinfunction "22/A8_22/A8") (pintype "bidirectional"))
    )
    (net (code "30") (name "/ENT5-6") (class "Default")
      (node (ref "R9") (pin "2") (pinfunction "2_2") (pintype "passive"))
      (node (ref "U$1") (pin "12/MISO") (pinfunction "12/MISO_12/MISO") (pintype "bidirectional"))
    )
    (net (code "31") (name "/ENT5A") (class "Default")
      (node (ref "IC3") (pin "2") (pinfunction "1A_2") (pintype "bidirectional"))
      (node (ref "U$1") (pin "10/CS") (pinfunction "10/CS_10/CS") (pintype "bidirectional"))
    )
    (net (code "32") (name "/ENT5B") (class "Default")
      (node (ref "IC3") (pin "7") (pinfunction "2A_7") (pintype "bidirectional"))
      (node (ref "U$1") (pin "9/CS") (pinfunction "9/CS_9/CS") (pintype "bidirectional"))
    )
    (net (code "33") (name "/ENT6A") (class "Default")
      (node (ref "IC3") (pin "10") (pinfunction "3A_10") (pintype "bidirectional"))
      (node (ref "U$1") (pin "7") (pinfunction "7_7") (pintype "bidirectional"))
    )
    (net (code "34") (name "/ENT6B") (class "Default")
      (node (ref "IC3") (pin "15") (pinfunction "4A_15") (pintype "bidirectional"))
      (node (ref "U$1") (pin "8") (pinfunction "8_8") (pintype "bidirectional"))
    )
    (net (code "35") (name "/ENT7-8") (class "Default")
      (node (ref "R11") (pin "2") (pinfunction "2_2") (pintype "passive"))
      (node (ref "U$1") (pin "11/MOSI") (pinfunction "11/MOSI_11/MOSI") (pintype "bidirectional"))
    )
    (net (code "36") (name "/ENT7A") (class "Default")
      (node (ref "IC4") (pin "2") (pinfunction "1A_2") (pintype "bidirectional"))
      (node (ref "U$1") (pin "6") (pinfunction "6_6") (pintype "bidirectional"))
    )
    (net (code "37") (name "/ENT7B") (class "Default")
      (node (ref "IC4") (pin "7") (pinfunction "2A_7") (pintype "bidirectional"))
      (node (ref "U$1") (pin "5") (pinfunction "5_5") (pintype "bidirectional"))
    )
    (net (code "38") (name "/ENT8A") (class "Default")
      (node (ref "IC4") (pin "10") (pinfunction "3A_10") (pintype "bidirectional"))
      (node (ref "U$1") (pin "3/CANTX") (pinfunction "3/CANTX_3/CANTX") (pintype "bidirectional"))
    )
    (net (code "39") (name "/ENT8B") (class "Default")
      (node (ref "IC4") (pin "15") (pinfunction "4A_15") (pintype "bidirectional"))
      (node (ref "U$1") (pin "4/CANRX") (pinfunction "4/CANRX_4/CANRX") (pintype "bidirectional"))
    )
    (net (code "40") (name "/EVAL_ACK") (class "Default")
      (node (ref "D1") (pin "3") (pinfunction "C_3") (pintype "passive"))
      (node (ref "R37") (pin "1") (pinfunction "1_1") (pintype "passive"))
      (node (ref "U$1") (pin "26") (pinfunction "26_26") (pintype "bidirectional"))
    )
    (net (code "41") (name "/INT") (class "Default")
      (node (ref "JP3") (pin "10") (pinfunction "10_10") (pintype "passive"))
      (node (ref "U$1") (pin "16/A2") (pinfunction "16/A2_16/A2") (pintype "bidirectional"))
    )
    (net (code "42") (name "/KEY") (class "Default")
      (node (ref "JP3") (pin "7") (pinfunction "7_7") (pintype "passive"))
      (node (ref "U$1") (pin "17/A3") (pinfunction "17/A3_17/A3") (pintype "bidirectional"))
    )
    (net (code "43") (name "/O1") (class "Default")
      (node (ref "IC5") (pin "11") (pinfunction "O8_11") (pintype "open_collector"))
      (node (ref "X11") (pin "7") (pinfunction "K_7") (pintype "passive"))
    )
    (net (code "44") (name "/O2") (class "Default")
      (node (ref "IC5") (pin "12") (pinfunction "O7_12") (pintype "open_collector"))
      (node (ref "X11") (pin "5") (pinfunction "K_5") (pintype "passive"))
    )
    (net (code "45") (name "/O3") (class "Default")
      (node (ref "IC5") (pin "13") (pinfunction "O6_13") (pintype "open_collector"))
      (node (ref "X11") (pin "3") (pinfunction "K_3") (pintype "passive"))
    )
    (net (code "46") (name "/O4") (class "Default")
      (node (ref "IC5") (pin "14") (pinfunction "O5_14") (pintype "open_collector"))
      (node (ref "X11") (pin "1") (pinfunction "K_1") (pintype "passive"))
    )
    (net (code "47") (name "/O5") (class "Default")
      (node (ref "IC5") (pin "15") (pinfunction "O4_15") (pintype "open_collector"))
      (node (ref "X10") (pin "7") (pinfunction "K_7") (pintype "passive"))
    )
    (net (code "48") (name "/O6") (class "Default")
      (node (ref "IC5") (pin "16") (pinfunction "O3_16") (pintype "open_collector"))
      (node (ref "X10") (pin "5") (pinfunction "K_5") (pintype "passive"))
    )
    (net (code "49") (name "/O7") (class "Default")
      (node (ref "IC5") (pin "17") (pinfunction "O2_17") (pintype "open_collector"))
      (node (ref "X10") (pin "3") (pinfunction "K_3") (pintype "passive"))
    )
    (net (code "50") (name "/O8") (class "Default")
      (node (ref "IC5") (pin "18") (pinfunction "O1_18") (pintype "open_collector"))
      (node (ref "X10") (pin "1") (pinfunction "K_1") (pintype "passive"))
    )
    (net (code "51") (name "/OC1-2") (class "Default")
      (node (ref "Q1") (pin "E") (pinfunction "E_E") (pintype "passive"))
      (node (ref "R4") (pin "2") (pinfunction "2_2") (pintype "passive"))
      (node (ref "U$1") (pin "33/A14") (pinfunction "33/A14_33/A14") (pintype "bidirectional"))
    )
    (net (code "52") (name "/OC3-4") (class "Default")
      (node (ref "Q2") (pin "E") (pinfunction "E_E") (pintype "passive"))
      (node (ref "R6") (pin "2") (pinfunction "2_2") (pintype "passive"))
      (node (ref "U$1") (pin "34/A15") (pinfunction "34/A15_34/A15") (pintype "bidirectional"))
    )
    (net (code "53") (name "/OC5-6") (class "Default")
      (node (ref "Q3") (pin "E") (pinfunction "E_E") (pintype "passive"))
      (node (ref "R8") (pin "2") (pinfunction "2_2") (pintype "passive"))
      (node (ref "U$1") (pin "35/A16") (pinfunction "35/A16_35/A16") (pintype "bidirectional"))
    )
    (net (code "54") (name "/OC7-8") (class "Default")
      (node (ref "Q4") (pin "E") (pinfunction "E_E") (pintype "passive"))
      (node (ref "R10") (pin "2") (pinfunction "2_2") (pintype "passive"))
      (node (ref "U$1") (pin "36/A17") (pinfunction "36/A17_36/A17") (pintype "bidirectional"))
    )
    (net (code "55") (name "/OT1A") (class "Default")
      (node (ref "IC1") (pin "3") (pinfunction "1Y_3") (pintype "bidirectional"))
      (node (ref "LED5") (pin "K") (pinfunction "C_K") (pintype "passive"))
      (node (ref "X1") (pin "3") (pinfunction "K_3") (pintype "passive"))
    )
    (net (code "56") (name "/OT1B") (class "Default")
      (node (ref "IC1") (pin "6") (pinfunction "2Y_6") (pintype "bidirectional"))
      (node (ref "LED13") (pin "K") (pinfunction "C_K") (pintype "passive"))
      (node (ref "X1") (pin "1") (pinfunction "K_1") (pintype "passive"))
    )
    (net (code "57") (name "/OT2A") (class "Default")
      (node (ref "IC1") (pin "11") (pinfunction "3Y_11") (pintype "bidirectional"))
      (node (ref "LED4") (pin "K") (pinfunction "C_K") (pintype "passive"))
      (node (ref "X1") (pin "6") (pinfunction "K_6") (pintype "passive"))
    )
    (net (code "58") (name "/OT2B") (class "Default")
      (node (ref "IC1") (pin "14") (pinfunction "4Y_14") (pintype "bidirectional"))
      (node (ref "LED12") (pin "K") (pinfunction "C_K") (pintype "passive"))
      (node (ref "X1") (pin "4") (pinfunction "K_4") (pintype "passive"))
    )
    (net (code "59") (name "/OT3A") (class "Default")
      (node (ref "IC2") (pin "3") (pinfunction "1Y_3") (pintype "bidirectional"))
      (node (ref "LED7") (pin "K") (pinfunction "C_K") (pintype "passive"))
      (node (ref "X2") (pin "3") (pinfunction "K_3") (pintype "passive"))
    )
    (net (code "60") (name "/OT3B") (class "Default")
      (node (ref "IC2") (pin "6") (pinfunction "2Y_6") (pintype "bidirectional"))
      (node (ref "LED15") (pin "K") (pinfunction "C_K") (pintype "passive"))
      (node (ref "X2") (pin "1") (pinfunction "K_1") (pintype "passive"))
    )
    (net (code "61") (name "/OT4A") (class "Default")
      (node (ref "IC2") (pin "11") (pinfunction "3Y_11") (pintype "bidirectional"))
      (node (ref "LED6") (pin "K") (pinfunction "C_K") (pintype "passive"))
      (node (ref "X2") (pin "6") (pinfunction "K_6") (pintype "passive"))
    )
    (net (code "62") (name "/OT4B") (class "Default")
      (node (ref "IC2") (pin "14") (pinfunction "4Y_14") (pintype "bidirectional"))
      (node (ref "LED14") (pin "K") (pinfunction "C_K") (pintype "passive"))
      (node (ref "X2") (pin "4") (pinfunction "K_4") (pintype "passive"))
    )
    (net (code "63") (name "/OT5A") (class "Default")
      (node (ref "IC3") (pin "3") (pinfunction "1Y_3") (pintype "bidirectional"))
      (node (ref "LED9") (pin "K") (pinfunction "C_K") (pintype "passive"))
      (node (ref "X3") (pin "3") (pinfunction "K_3") (pintype "passive"))
    )
    (net (code "64") (name "/OT5B") (class "Default")
      (node (ref "IC3") (pin "6") (pinfunction "2Y_6") (pintype "bidirectional"))
      (node (ref "LED17") (pin "K") (pinfunction "C_K") (pintype "passive"))
      (node (ref "X3") (pin "1") (pinfunction "K_1") (pintype "passive"))
    )
    (net (code "65") (name "/OT6A") (class "Default")
      (node (ref "IC3") (pin "11") (pinfunction "3Y_11") (pintype "bidirectional"))
      (node (ref "LED8") (pin "K") (pinfunction "C_K") (pintype "passive"))
      (node (ref "X3") (pin "6") (pinfunction "K_6") (pintype "passive"))
    )
    (net (code "66") (name "/OT6B") (class "Default")
      (node (ref "IC3") (pin "14") (pinfunction "4Y_14") (pintype "bidirectional"))
      (node (ref "LED16") (pin "K") (pinfunction "C_K") (pintype "passive"))
      (node (ref "X3") (pin "4") (pinfunction "K_4") (pintype "passive"))
    )
    (net (code "67") (name "/OT7A") (class "Default")
      (node (ref "IC4") (pin "3") (pinfunction "1Y_3") (pintype "bidirectional"))
      (node (ref "LED11") (pin "K") (pinfunction "C_K") (pintype "passive"))
      (node (ref "X4") (pin "3") (pinfunction "K_3") (pintype "passive"))
    )
    (net (code "68") (name "/OT7B") (class "Default")
      (node (ref "IC4") (pin "6") (pinfunction "2Y_6") (pintype "bidirectional"))
      (node (ref "LED19") (pin "K") (pinfunction "C_K") (pintype "passive"))
      (node (ref "X4") (pin "1") (pinfunction "K_1") (pintype "passive"))
    )
    (net (code "69") (name "/OT8A") (class "Default")
      (node (ref "IC4") (pin "11") (pinfunction "3Y_11") (pintype "bidirectional"))
      (node (ref "LED10") (pin "K") (pinfunction "C_K") (pintype "passive"))
      (node (ref "X4") (pin "6") (pinfunction "K_6") (pintype "passive"))
    )
    (net (code "70") (name "/OT8B") (class "Default")
      (node (ref "IC4") (pin "14") (pinfunction "4Y_14") (pintype "bidirectional"))
      (node (ref "LED18") (pin "K") (pinfunction "C_K") (pintype "passive"))
      (node (ref "X4") (pin "4") (pinfunction "K_4") (pintype "passive"))
    )
    (net (code "71") (name "/RED") (class "Default")
      (node (ref "LED1") (pin "K") (pinfunction "C_K") (pintype "passive"))
      (node (ref "U$1") (pin "38/A19") (pinfunction "38/A19_38/A19") (pintype "bidirectional"))
    )
    (net (code "72") (name "/RX") (class "Default")
      (node (ref "JP3") (pin "1") (pinfunction "1_1") (pintype "passive"))
      (node (ref "U$1") (pin "0/RX") (pinfunction "0/RX_0/RX") (pintype "bidirectional"))
    )
    (net (code "73") (name "/SCL") (class "Default")
      (node (ref "J1") (pin "1") (pinfunction "1_1") (pintype "bidirectional"))
      (node (ref "JP3") (pin "2") (pinfunction "2_2") (pintype "passive"))
      (node (ref "R16") (pin "1") (pinfunction "1_1") (pintype "passive"))
      (node (ref "U$1") (pin "18/A4/SDA") (pinfunction "18/A4/SDA_18/A4/SDA") (pintype "bidirectional"))
      (node (ref "U2") (pin "1") (pinfunction "SCL_1") (pintype "input"))
      (node (ref "Z7") (pin "C") (pinfunction "C_C") (pintype "passive"))
    )
    (net (code "74") (name "/SDA") (class "Default")
      (node (ref "J1") (pin "2") (pinfunction "2_2") (pintype "bidirectional"))
      (node (ref "JP3") (pin "6") (pinfunction "6_6") (pintype "passive"))
      (node (ref "R17") (pin "1") (pinfunction "1_1") (pintype "passive"))
      (node (ref "U$1") (pin "19/A5/SCL") (pinfunction "19/A5/SCL_19/A5/SCL") (pintype "bidirectional"))
      (node (ref "U2") (pin "2") (pinfunction "SDA_2") (pintype "bidirectional"))
      (node (ref "Z6") (pin "C") (pinfunction "C_C") (pintype "passive"))
    )
    (net (code "75") (name "/TRACK1") (class "Default")
      (node (ref "R1") (pin "2") (pinfunction "2_2") (pintype "passive"))
      (node (ref "X9") (pin "1") (pinfunction "KL_1") (pintype "passive"))
    )
    (net (code "76") (name "/TRACK2") (class "Default")
      (node (ref "C1") (pin "2") (pinfunction "2_2") (pintype "passive"))
      (node (ref "D7") (pin "A") (pinfunction "A_A") (pintype "passive"))
      (node (ref "OK1") (pin "3") (pinfunction "C_3") (pintype "passive"))
      (node (ref "X9") (pin "2") (pinfunction "KL_2") (pintype "passive"))
    )
    (net (code "77") (name "/TX") (class "Default")
      (node (ref "JP3") (pin "3") (pinfunction "3_3") (pintype "passive"))
      (node (ref "U$1") (pin "1/TX") (pinfunction "1/TX_1/TX") (pintype "bidirectional"))
    )
    (net (code "78") (name "/XPA") (class "Default")
      (node (ref "IC6") (pin "6") (pinfunction "A_6") (pintype "bidirectional"))
      (node (ref "J4") (pin "4") (pinfunction "4_4") (pintype "passive"))
      (node (ref "J5") (pin "4") (pinfunction "4_4") (pintype "passive"))
      (node (ref "JP2") (pin "1") (pinfunction "1_1") (pintype "passive"))
      (node (ref "R12") (pin "1") (pinfunction "1_1") (pintype "passive"))
    )
    (net (code "79") (name "/XPB") (class "Default")
      (node (ref "IC6") (pin "7") (pinfunction "B_7") (pintype "bidirectional"))
      (node (ref "J4") (pin "3") (pinfunction "3_3") (pintype "passive"))
      (node (ref "J5") (pin "3") (pinfunction "3_3") (pintype "passive"))
      (node (ref "R34") (pin "2") (pinfunction "2_2") (pintype "passive"))
      (node (ref "R35") (pin "1") (pinfunction "1_1") (pintype "passive"))
    )
    (net (code "80") (name "/XP_DIR") (class "Default")
      (node (ref "IC6") (pin "2") (pinfunction "~{RE}_2") (pintype "input"))
      (node (ref "IC6") (pin "3") (pinfunction "DE_3") (pintype "input"))
      (node (ref "U$1") (pin "28") (pinfunction "28_28") (pintype "bidirectional"))
    )
    (net (code "81") (name "/XP_RX") (class "Default")
      (node (ref "IC6") (pin "1") (pinfunction "RO_1") (pintype "output"))
      (node (ref "U$1") (pin "31/A12") (pinfunction "31/A12_31/A12") (pintype "bidirectional"))
    )
    (net (code "82") (name "/XP_TX") (class "Default")
      (node (ref "IC6") (pin "4") (pinfunction "DI_4") (pintype "input"))
      (node (ref "U$1") (pin "32/A13") (pinfunction "32/A13_32/A13") (pintype "bidirectional"))
    )
    (net (code "83") (name "/~{RST}") (class "Default")
      (node (ref "U$1") (pin "RESET") (pinfunction "RESET_RESET") (pintype "bidirectional"))
      (node (ref "U2") (pin "15") (pinfunction "~{RST}_15") (pintype "input"))
    )
    (net (code "84") (name "GND") (class "Default")
      (node (ref "C14") (pin "2") (pinfunction "2_2") (pintype "passive"))
      (node (ref "C15") (pin "2") (pinfunction "2_2") (pintype "passive"))
      (node (ref "C16") (pin "2") (pinfunction "2_2") (pintype "passive"))
      (node (ref "C17") (pin "2") (pinfunction "2_2") (pintype "passive"))
      (node (ref "C18") (pin "2") (pinfunction "2_2") (pintype "passive"))
      (node (ref "C19") (pin "2") (pinfunction "2_2") (pintype "passive"))
      (node (ref "C2") (pin "2") (pinfunction "2_2") (pintype "passive"))
      (node (ref "C20") (pin "2") (pinfunction "2_2") (pintype "passive"))
      (node (ref "C21") (pin "2") (pinfunction "2_2") (pintype "passive"))
      (node (ref "C3") (pin "2") (pinfunction "2_2") (pintype "passive"))
      (node (ref "C5") (pin "2") (pinfunction "2_2") (pintype "passive"))
      (node (ref "C6") (pin "-") (pinfunction "-_-") (pintype "passive"))
      (node (ref "C7") (pin "2") (pinfunction "2_2") (pintype "passive"))
      (node (ref "C8") (pin "-") (pinfunction "-_-") (pintype "passive"))
      (node (ref "D1") (pin "1") (pinfunction "A_1") (pintype "passive"))
      (node (ref "D3") (pin "A") (pinfunction "A_A") (pintype "passive"))
      (node (ref "D4") (pin "A") (pinfunction "A_A") (pintype "passive"))
      (node (ref "D5") (pin "A") (pinfunction "A_A") (pintype "passive"))
      (node (ref "D6") (pin "A") (pinfunction "A_A") (pintype "passive"))
      (node (ref "GND") (pin "TP") (pinfunction "TP_TP") (pintype "input"))
      (node (ref "H2") (pin "B3,2") (pinfunction "MOUNT_B3,2") (pintype "passive"))
      (node (ref "IC1") (pin "12") (pinfunction "GND_12") (pintype "bidirectional"))
      (node (ref "IC1") (pin "13") (pinfunction "GND_13") (pintype "bidirectional"))
      (node (ref "IC1") (pin "4") (pinfunction "GND_4") (pintype "bidirectional"))
      (node (ref "IC1") (pin "5") (pinfunction "GND_5") (pintype "bidirectional"))
      (node (ref "IC2") (pin "12") (pinfunction "GND_12") (pintype "bidirectional"))
      (node (ref "IC2") (pin "13") (pinfunction "GND_13") (pintype "bidirectional"))
      (node (ref "IC2") (pin "4") (pinfunction "GND_4") (pintype "bidirectional"))
      (node (ref "IC2") (pin "5") (pinfunction "GND_5") (pintype "bidirectional"))
      (node (ref "IC3") (pin "12") (pinfunction "GND_12") (pintype "bidirectional"))
      (node (ref "IC3") (pin "13") (pinfunction "GND_13") (pintype "bidirectional"))
      (node (ref "IC3") (pin "4") (pinfunction "GND_4") (pintype "bidirectional"))
      (node (ref "IC3") (pin "5") (pinfunction "GND_5") (pintype "bidirectional"))
      (node (ref "IC4") (pin "12") (pinfunction "GND_12") (pintype "bidirectional"))
      (node (ref "IC4") (pin "13") (pinfunction "GND_13") (pintype "bidirectional"))
      (node (ref "IC4") (pin "4") (pinfunction "GND_4") (pintype "bidirectional"))
      (node (ref "IC4") (pin "5") (pinfunction "GND_5") (pintype "bidirectional"))
      (node (ref "IC5") (pin "9") (pinfunction "GND_9") (pintype "power_in"))
      (node (ref "IC6") (pin "5") (pinfunction "GND_5") (pintype "input"))
      (node (ref "J1") (pin "4") (pinfunction "4_4") (pintype "bidirectional"))
      (node (ref "J2") (pin "4") (pinfunction "4_4") (pintype "bidirectional"))
      (node (ref "J3") (pin "4") (pinfunction "4_4") (pintype "bidirectional"))
      (node (ref "J4") (pin "2") (pinfunction "2_2") (pintype "passive"))
      (node (ref "J5") (pin "2") (pinfunction "2_2") (pintype "passive"))
      (node (ref "JP3") (pin "4") (pinfunction "4_4") (pintype "passive"))
      (node (ref "JP3") (pin "9") (pinfunction "9_9") (pintype "passive"))
      (node (ref "LED3") (pin "K") (pinfunction "C_K") (pintype "passive"))
      (node (ref "MT1") (pin "1") (pinfunction "GND_1") (pintype "passive"))
      (node (ref "MT2") (pin "1") (pinfunction "GND_1") (pintype "passive"))
      (node (ref "OK1") (pin "5") (pinfunction "GND_5") (pintype "passive"))
      (node (ref "Q6") (pin "2") (pinfunction "S_2") (pintype "passive"))
      (node (ref "R10") (pin "1") (pinfunction "1_1") (pintype "passive"))
      (node (ref "R34") (pin "1") (pinfunction "1_1") (pintype "passive"))
      (node (ref "R4") (pin "1") (pinfunction "1_1") (pintype "passive"))
      (node (ref "R6") (pin "1") (pinfunction "1_1") (pintype "passive"))
      (node (ref "R8") (pin "1") (pinfunction "1_1") (pintype "passive"))
      (node (ref "SJ2") (pin "1") (pinfunction "1_1") (pintype "passive"))
      (node (ref "U$1") (pin "AGND") (pinfunction "AGND_AGND") (pintype "bidirectional"))
      (node (ref "U$1") (pin "GND") (pinfunction "GND_GND") (pintype "bidirectional"))
      (node (ref "U$1") (pin "GND2") (pinfunction "GND2_GND2") (pintype "bidirectional"))
      (node (ref "U$1") (pin "GND3") (pinfunction "GND3_GND3") (pintype "bidirectional"))
      (node (ref "U1") (pin "4") (pinfunction "G_4") (pintype "passive"))
      (node (ref "U2") (pin "3") (pinfunction "A0_3") (pintype "input"))
      (node (ref "U2") (pin "4") (pinfunction "A1_4") (pintype "input"))
      (node (ref "U2") (pin "5") (pinfunction "A2_5") (pintype "input"))
      (node (ref "U2") (pin "8") (pinfunction "GND_8") (pintype "passive"))
      (node (ref "U3") (pin "GND") (pinfunction "GND_GND") (pintype "input"))
      (node (ref "X10") (pin "8") (pinfunction "K_8") (pintype "passive"))
      (node (ref "X11") (pin "8") (pinfunction "K_8") (pintype "passive"))
      (node (ref "X9") (pin "4") (pinfunction "KL_4") (pintype "passive"))
      (node (ref "Z1") (pin "2") (pinfunction "A_2") (pintype "passive"))
      (node (ref "Z2") (pin "A") (pinfunction "A_A") (pintype "passive"))
      (node (ref "Z3") (pin "A") (pinfunction "A_A") (pintype "passive"))
      (node (ref "Z4") (pin "A") (pinfunction "A_A") (pintype "passive"))
      (node (ref "Z5") (pin "A") (pinfunction "A_A") (pintype "passive"))
      (node (ref "Z6") (pin "A") (pinfunction "A_A") (pintype "passive"))
      (node (ref "Z7") (pin "A") (pinfunction "A_A") (pintype "passive"))
    )
    (net (code "85") (name "Net-(C5-Pad1)") (class "Default")
      (node (ref "C5") (pin "1") (pinfunction "1_1") (pintype "passive"))
      (node (ref "L1") (pin "2") (pinfunction "2_2") (pintype "passive"))
      (node (ref "U$1") (pin "AREF") (pinfunction "AREF_AREF") (pintype "bidirectional"))
    )
    (net (code "86") (name "Net-(IC5-CD+)") (class "Default")
      (node (ref "F1") (pin "2") (pinfunction "2_2") (pintype "passive"))
      (node (ref "IC5") (pin "10") (pinfunction "CD+_10") (pintype "passive"))
      (node (ref "X10") (pin "2") (pinfunction "K_2") (pintype "passive"))
      (node (ref "X10") (pin "4") (pinfunction "K_4") (pintype "passive"))
      (node (ref "X10") (pin "6") (pinfunction "K_6") (pintype "passive"))
      (node (ref "X11") (pin "2") (pinfunction "K_2") (pintype "passive"))
      (node (ref "X11") (pin "4") (pinfunction "K_4") (pintype "passive"))
      (node (ref "X11") (pin "6") (pinfunction "K_6") (pintype "passive"))
    )
    (net (code "87") (name "Net-(J4-Pad1)") (class "Default")
      (node (ref "J4") (pin "1") (pinfunction "1_1") (pintype "passive"))
      (node (ref "J5") (pin "1") (pinfunction "1_1") (pintype "passive"))
      (node (ref "SJ2") (pin "2") (pinfunction "2_2") (pintype "passive"))
    )
    (net (code "88") (name "Net-(J4-Pad6)") (class "Default")
      (node (ref "J4") (pin "6") (pinfunction "6_6") (pintype "passive"))
      (node (ref "J5") (pin "6") (pinfunction "6_6") (pintype "passive"))
      (node (ref "SJ1") (pin "2") (pinfunction "2_2") (pintype "passive"))
    )
    (net (code "89") (name "Net-(JP2-Pad2)") (class "Default")
      (node (ref "JP2") (pin "2") (pinfunction "2_2") (pintype "passive"))
      (node (ref "R35") (pin "2") (pinfunction "2_2") (pintype "passive"))
    )
    (net (code "90") (name "Net-(LED1-PadA)") (class "Default")
      (node (ref "LED1") (pin "A") (pinfunction "A_A") (pintype "passive"))
      (node (ref "R13") (pin "1") (pinfunction "1_1") (pintype "passive"))
    )
    (net (code "91") (name "Net-(LED2-PadA)") (class "Default")
      (node (ref "LED2") (pin "A") (pinfunction "A_A") (pintype "passive"))
      (node (ref "R14") (pin "1") (pinfunction "1_1") (pintype "passive"))
    )
    (net (code "92") (name "Net-(LED3-PadA)") (class "Default")
      (node (ref "LED3") (pin "A") (pinfunction "A_A") (pintype "passive"))
      (node (ref "R15") (pin "1") (pinfunction "1_1") (pintype "passive"))
    )
    (net (code "93") (name "Net-(LED4-PadA)") (class "Default")
      (node (ref "LED4") (pin "A") (pinfunction "A_A") (pintype "passive"))
      (node (ref "R18") (pin "1") (pinfunction "1_1") (pintype "passive"))
    )
    (net (code "94") (name "Net-(LED5-PadA)") (class "Default")
      (node (ref "LED5") (pin "A") (pinfunction "A_A") (pintype "passive"))
      (node (ref "R19") (pin "1") (pinfunction "1_1") (pintype "passive"))
    )
    (net (code "95") (name "Net-(LED6-PadA)") (class "Default")
      (node (ref "LED6") (pin "A") (pinfunction "A_A") (pintype "passive"))
      (node (ref "R20") (pin "1") (pinfunction "1_1") (pintype "passive"))
    )
    (net (code "96") (name "Net-(LED7-PadA)") (class "Default")
      (node (ref "LED7") (pin "A") (pinfunction "A_A") (pintype "passive"))
      (node (ref "R21") (pin "1") (pinfunction "1_1") (pintype "passive"))
    )
    (net (code "97") (name "Net-(LED8-PadA)") (class "Default")
      (node (ref "LED8") (pin "A") (pinfunction "A_A") (pintype "passive"))
      (node (ref "R22") (pin "1") (pinfunction "1_1") (pintype "passive"))
    )
    (net (code "98") (name "Net-(LED9-PadA)") (class "Default")
      (node (ref "LED9") (pin "A") (pinfunction "A_A") (pintype "passive"))
      (node (ref "R23") (pin "1") (pinfunction "1_1") (pintype "passive"))
    )
    (net (code "99") (name "Net-(LED10-PadA)") (class "Default")
      (node (ref "LED10") (pin "A") (pinfunction "A_A") (pintype "passive"))
      (node (ref "R24") (pin "1") (pinfunction "1_1") (pintype "passive"))
    )
    (net (code "100") (name "Net-(LED11-PadA)") (class "Default")
      (node (ref "LED11") (pin "A") (pinfunction "A_A") (pintype "passive"))
      (node (ref "R25") (pin "1") (pinfunction "1_1") (pintype "passive"))
    )
    (net (code "101") (name "Net-(LED12-PadA)") (class "Default")
      (node (ref "LED12") (pin "A") (pinfunction "A_A") (pintype "passive"))
      (node (ref "R26") (pin "1") (pinfunction "1_1") (pintype "passive"))
    )
    (net (code "102") (name "Net-(LED13-PadA)") (class "Default")
      (node (ref "LED13") (pin "A") (pinfunction "A_A") (pintype "passive"))
      (node (ref "R27") (pin "1") (pinfunction "1_1") (pintype "passive"))
    )
    (net (code "103") (name "Net-(LED14-PadA)") (class "Default")
      (node (ref "LED14") (pin "A") (pinfunction "A_A") (pintype "passive"))
      (node (ref "R28") (pin "1") (pinfunction "1_1") (pintype "passive"))
    )
    (net (code "104") (name "Net-(LED15-PadA)") (class "Default")
      (node (ref "LED15") (pin "A") (pinfunction "A_A") (pintype "passive"))
      (node (ref "R29") (pin "1") (pinfunction "1_1") (pintype "passive"))
    )
    (net (code "105") (name "Net-(LED16-PadA)") (class "Default")
      (node (ref "LED16") (pin "A") (pinfunction "A_A") (pintype "passive"))
      (node (ref "R30") (pin "1") (pinfunction "1_1") (pintype "passive"))
    )
    (net (code "106") (name "Net-(LED17-PadA)") (class "Default")
      (node (ref "LED17") (pin "A") (pinfunction "A_A") (pintype "passive"))
      (node (ref "R31") (pin "1") (pinfunction "1_1") (pintype "passive"))
    )
    (net (code "107") (name "Net-(LED18-PadA)") (class "Default")
      (node (ref "LED18") (pin "A") (pinfunction "A_A") (pintype "passive"))
      (node (ref "R32") (pin "1") (pinfunction "1_1") (pintype "passive"))
    )
    (net (code "108") (name "Net-(LED19-PadA)") (class "Default")
      (node (ref "LED19") (pin "A") (pinfunction "A_A") (pintype "passive"))
      (node (ref "R33") (pin "1") (pinfunction "1_1") (pintype "passive"))
    )
    (net (code "109") (name "Net-(OK1-A)") (class "Default")
      (node (ref "C1") (pin "1") (pinfunction "1_1") (pintype "passive"))
      (node (ref "D7") (pin "C") (pinfunction "C_C") (pintype "passive"))
      (node (ref "OK1") (pin "2") (pinfunction "A_2") (pintype "passive"))
      (node (ref "R1") (pin "1") (pinfunction "1_1") (pintype "passive"))
    )
    (net (code "110") (name "Net-(OK1-VE)") (class "Default")
      (node (ref "OK1") (pin "7") (pinfunction "VE_7") (pintype "passive"))
      (node (ref "R2") (pin "1") (pinfunction "1_1") (pintype "passive"))
    )
    (net (code "111") (name "Net-(Q1-PadB)") (class "Default")
      (node (ref "Q1") (pin "B") (pinfunction "B_B") (pintype "passive"))
      (node (ref "R5") (pin "1") (pinfunction "1_1") (pintype "passive"))
    )
    (net (code "112") (name "Net-(Q2-PadB)") (class "Default")
      (node (ref "Q2") (pin "B") (pinfunction "B_B") (pintype "passive"))
      (node (ref "R7") (pin "1") (pinfunction "1_1") (pintype "passive"))
    )
    (net (code "113") (name "Net-(Q3-PadB)") (class "Default")
      (node (ref "Q3") (pin "B") (pinfunction "B_B") (pintype "passive"))
      (node (ref "R9") (pin "1") (pinfunction "1_1") (pintype "passive"))
    )
    (net (code "114") (name "Net-(Q4-PadB)") (class "Default")
      (node (ref "Q4") (pin "B") (pinfunction "B_B") (pintype "passive"))
      (node (ref "R11") (pin "1") (pinfunction "1_1") (pintype "passive"))
    )
    (net (code "115") (name "Net-(Q6-D)") (class "Default")
      (node (ref "Q6") (pin "3") (pinfunction "D_3") (pintype "passive"))
      (node (ref "R36") (pin "1") (pinfunction "1_1") (pintype "passive"))
    )
    (net (code "116") (name "Net-(U1-D1)") (class "Default")
      (node (ref "U1") (pin "5") (pinfunction "D4_5") (pintype "passive"))
      (node (ref "U1") (pin "6") (pinfunction "D3_6") (pintype "passive"))
      (node (ref "U1") (pin "7") (pinfunction "D2_7") (pintype "passive"))
      (node (ref "U1") (pin "8") (pinfunction "D1_8") (pintype "passive"))
      (node (ref "X9") (pin "3") (pinfunction "KL_3") (pintype "passive"))
      (node (ref "Z1") (pin "1") (pinfunction "C_1") (pintype "passive"))
    )
    (net (code "117") (name "Net-(X1B-K)") (class "Default")
      (node (ref "D3") (pin "C") (pinfunction "C_C") (pintype "passive"))
      (node (ref "Q1") (pin "C") (pinfunction "C_C") (pintype "passive"))
      (node (ref "X1") (pin "2") (pinfunction "K_2") (pintype "passive"))
      (node (ref "X1") (pin "5") (pinfunction "K_5") (pintype "passive"))
    )
    (net (code "118") (name "Net-(X2B-K)") (class "Default")
      (node (ref "D4") (pin "C") (pinfunction "C_C") (pintype "passive"))
      (node (ref "Q2") (pin "C") (pinfunction "C_C") (pintype "passive"))
      (node (ref "X2") (pin "2") (pinfunction "K_2") (pintype "passive"))
      (node (ref "X2") (pin "5") (pinfunction "K_5") (pintype "passive"))
    )
    (net (code "119") (name "Net-(X3B-K)") (class "Default")
      (node (ref "D6") (pin "C") (pinfunction "C_C") (pintype "passive"))
      (node (ref "Q3") (pin "C") (pinfunction "C_C") (pintype "passive"))
      (node (ref "X3") (pin "2") (pinfunction "K_2") (pintype "passive"))
      (node (ref "X3") (pin "5") (pinfunction "K_5") (pintype "passive"))
    )
    (net (code "120") (name "Net-(X4B-K)") (class "Default")
      (node (ref "D5") (pin "C") (pinfunction "C_C") (pintype "passive"))
      (node (ref "Q4") (pin "C") (pinfunction "C_C") (pintype "passive"))
      (node (ref "X4") (pin "2") (pinfunction "K_2") (pintype "passive"))
      (node (ref "X4") (pin "5") (pinfunction "K_5") (pintype "passive"))
    )
    (net (code "121") (name "unconnected-(H1-MOUNT-PadB3,2)") (class "Default")
      (node (ref "H1") (pin "B3,2") (pinfunction "MOUNT_B3,2") (pintype "passive"))
    )
    (net (code "122") (name "unconnected-(H3-MOUNT-PadB3,2)") (class "Default")
      (node (ref "H3") (pin "B3,2") (pinfunction "MOUNT_B3,2") (pintype "passive"))
    )
    (net (code "123") (name "unconnected-(H4-MOUNT-PadB3,2)") (class "Default")
      (node (ref "H4") (pin "B3,2") (pinfunction "MOUNT_B3,2") (pintype "passive"))
    )
    (net (code "124") (name "unconnected-(JP3-Pad8)") (class "Default")
      (node (ref "JP3") (pin "8") (pinfunction "8_8") (pintype "passive"))
    )
    (net (code "125") (name "unconnected-(U$1-Pad13{slash}SCK)") (class "Default")
      (node (ref "U$1") (pin "13/SCK") (pinfunction "13/SCK_13/SCK") (pintype "bidirectional"))
    )
    (net (code "126") (name "unconnected-(U$1-PadPROG)") (class "Default")
      (node (ref "U$1") (pin "PROG") (pinfunction "PROG_PROG") (pintype "bidirectional"))
    )
    (net (code "127") (name "unconnected-(U$1-PadU5V)") (class "Default")
      (node (ref "U$1") (pin "U5V") (pinfunction "U5V_U5V") (pintype "bidirectional"))
    )
    (net (code "128") (name "unconnected-(U$1-PadUD+)") (class "Default")
      (node (ref "U$1") (pin "UD+") (pinfunction "UD+_UD+") (pintype "bidirectional"))
    )
    (net (code "129") (name "unconnected-(U$1-PadUD-)") (class "Default")
      (node (ref "U$1") (pin "UD-") (pinfunction "UD-_UD-") (pintype "bidirectional"))
    )
    (net (code "130") (name "unconnected-(U$1-PadUGND1)") (class "Default")
      (node (ref "U$1") (pin "UGND1") (pinfunction "UGND1_UGND1") (pintype "bidirectional"))
    )
    (net (code "131") (name "unconnected-(U$1-PadUGND2)") (class "Default")
      (node (ref "U$1") (pin "UGND2") (pinfunction "UGND2_UGND2") (pintype "bidirectional"))
    )
    (net (code "132") (name "unconnected-(U$1-PadVBAT)") (class "Default")
      (node (ref "U$1") (pin "VBAT") (pinfunction "VBAT_VBAT") (pintype "bidirectional"))
    )
    (net (code "133") (name "unconnected-(U$1-PadVUSB)") (class "Default")
      (node (ref "U$1") (pin "VUSB") (pinfunction "VUSB_VUSB") (pintype "bidirectional"))
    )
  )
)
